# S7G7_footprint_simplified_w_ethernet_v1p.net
KiCad netlist of a schematic drawn in EAGLE
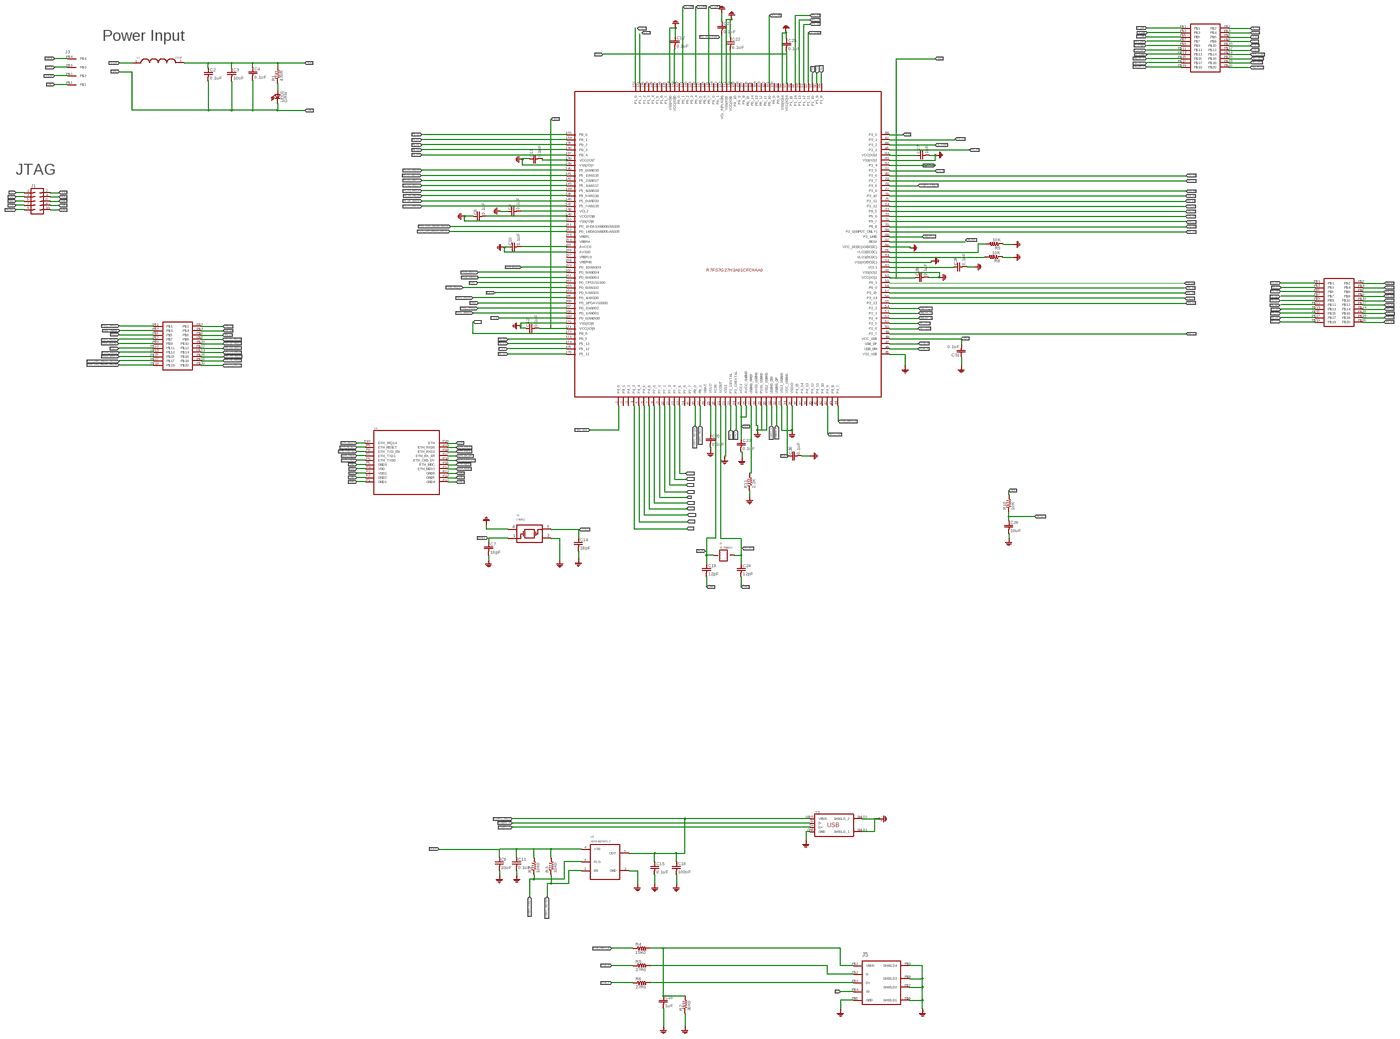
[diagram p0: schematic, sheet 1, overview]
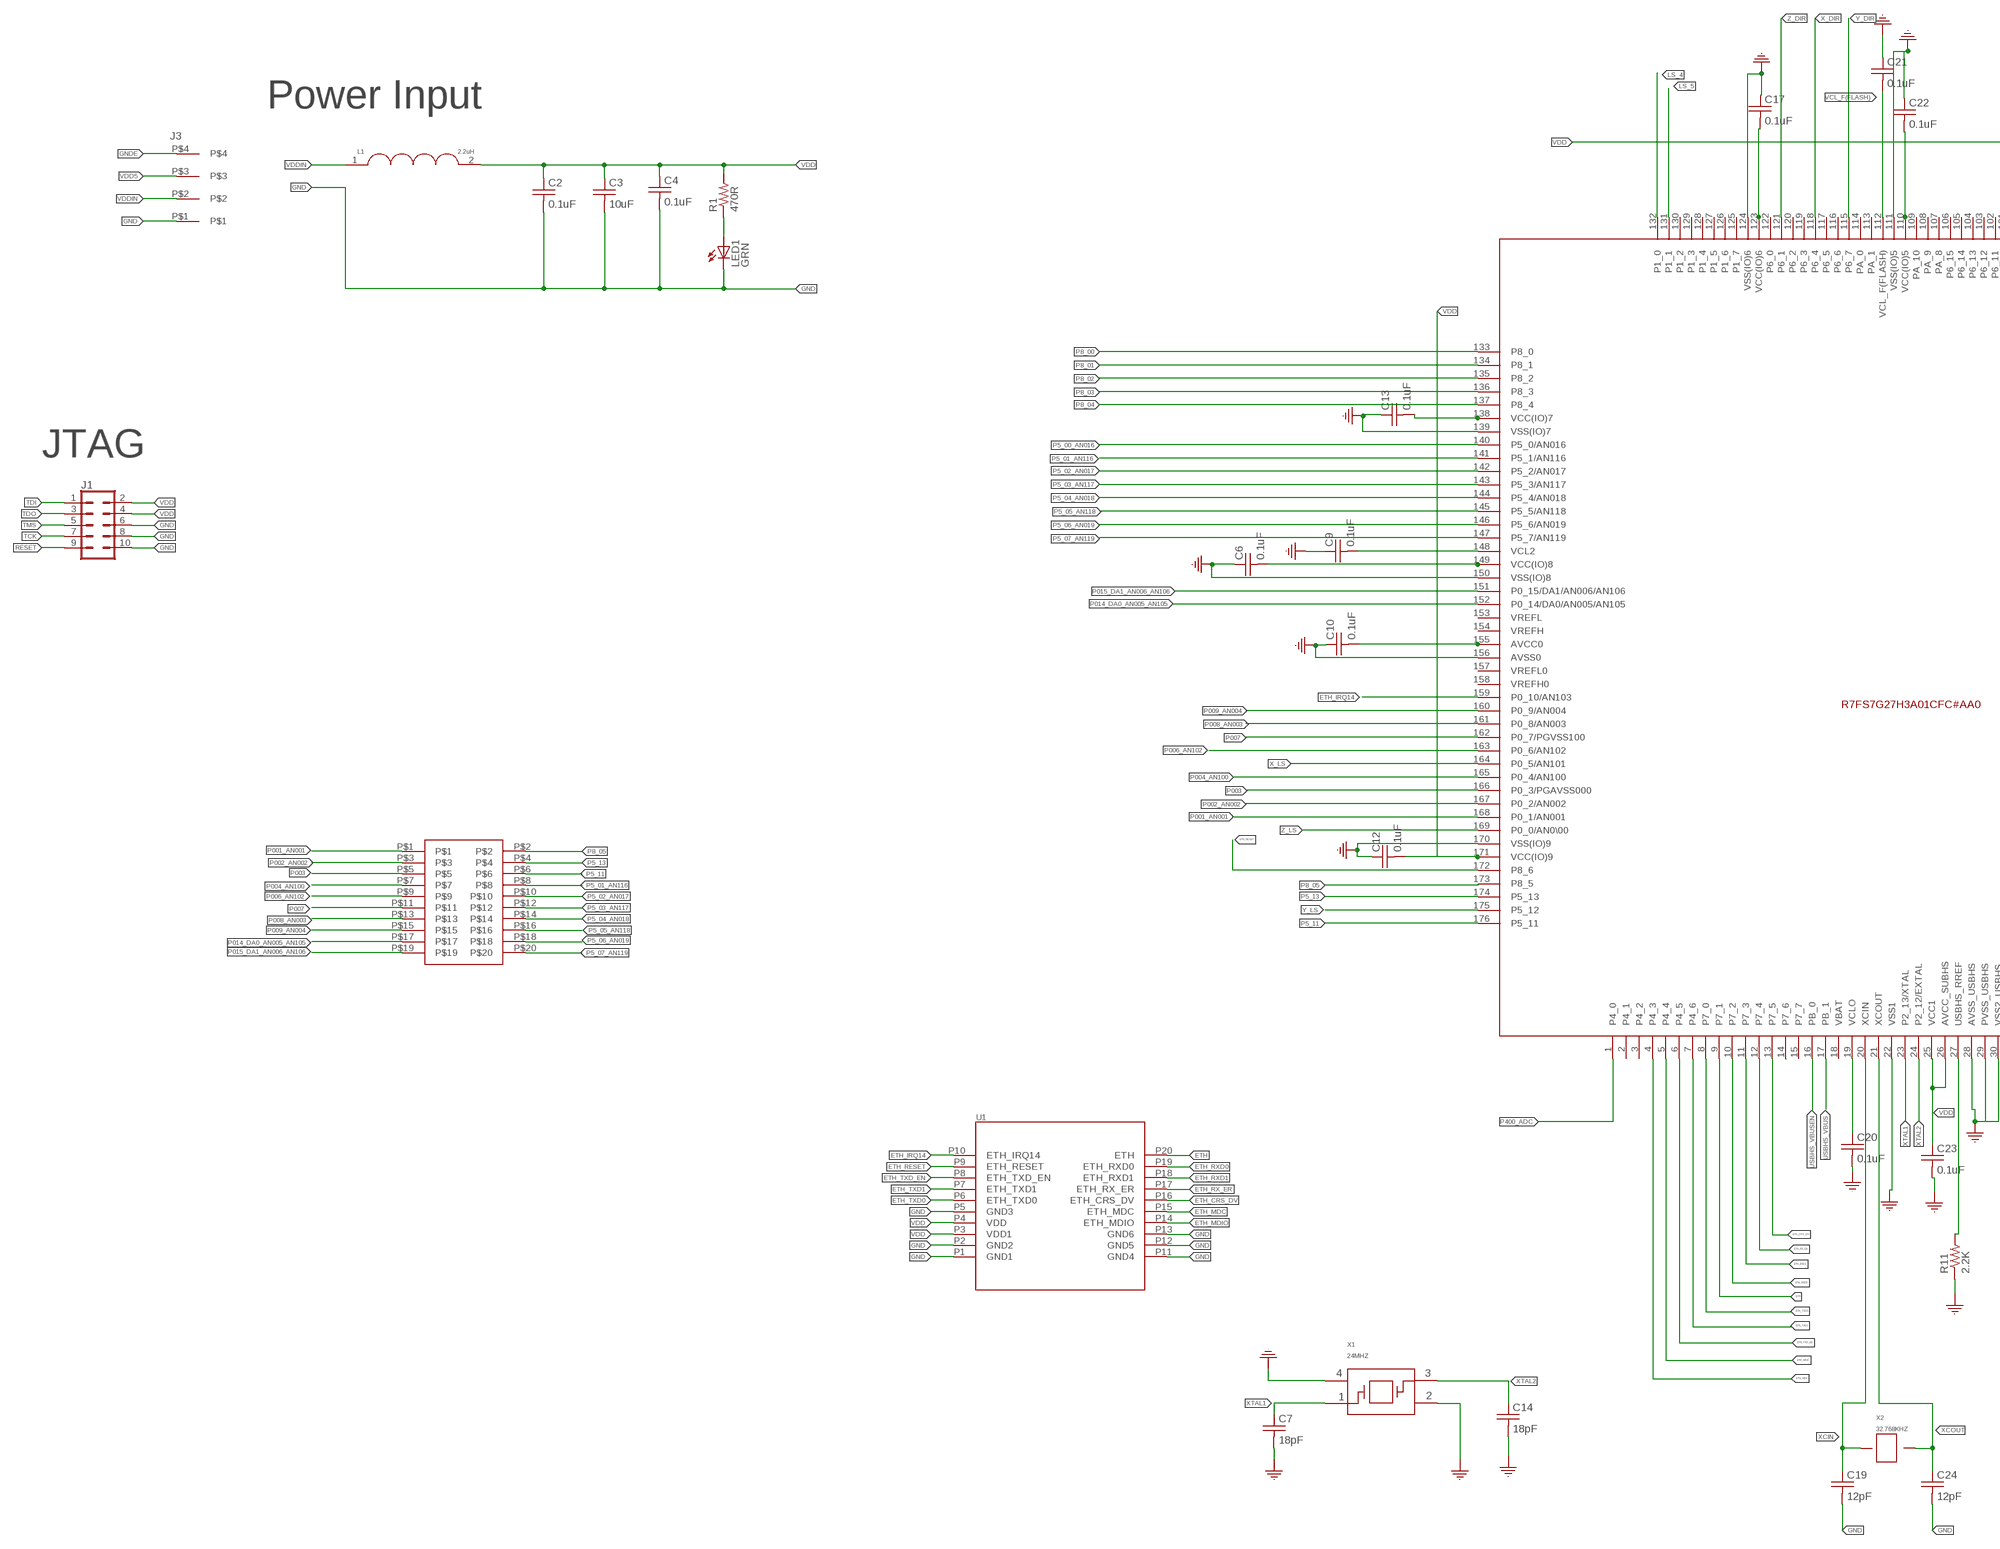
[diagram p1: schematic, sheet 1, part 1 of 4]
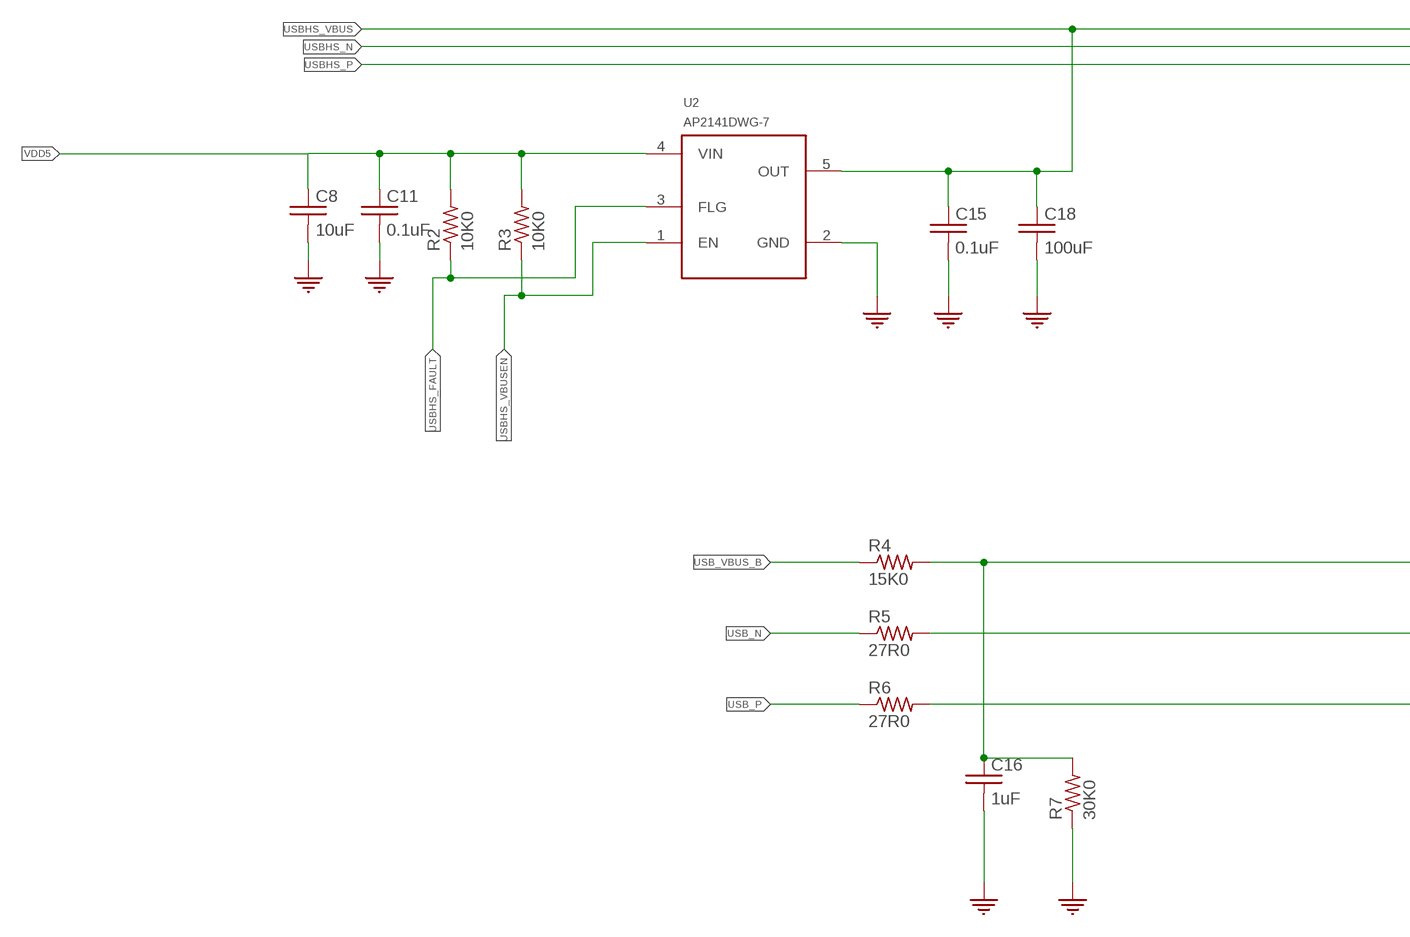
[diagram p2: schematic, sheet 1, part 2 of 4]
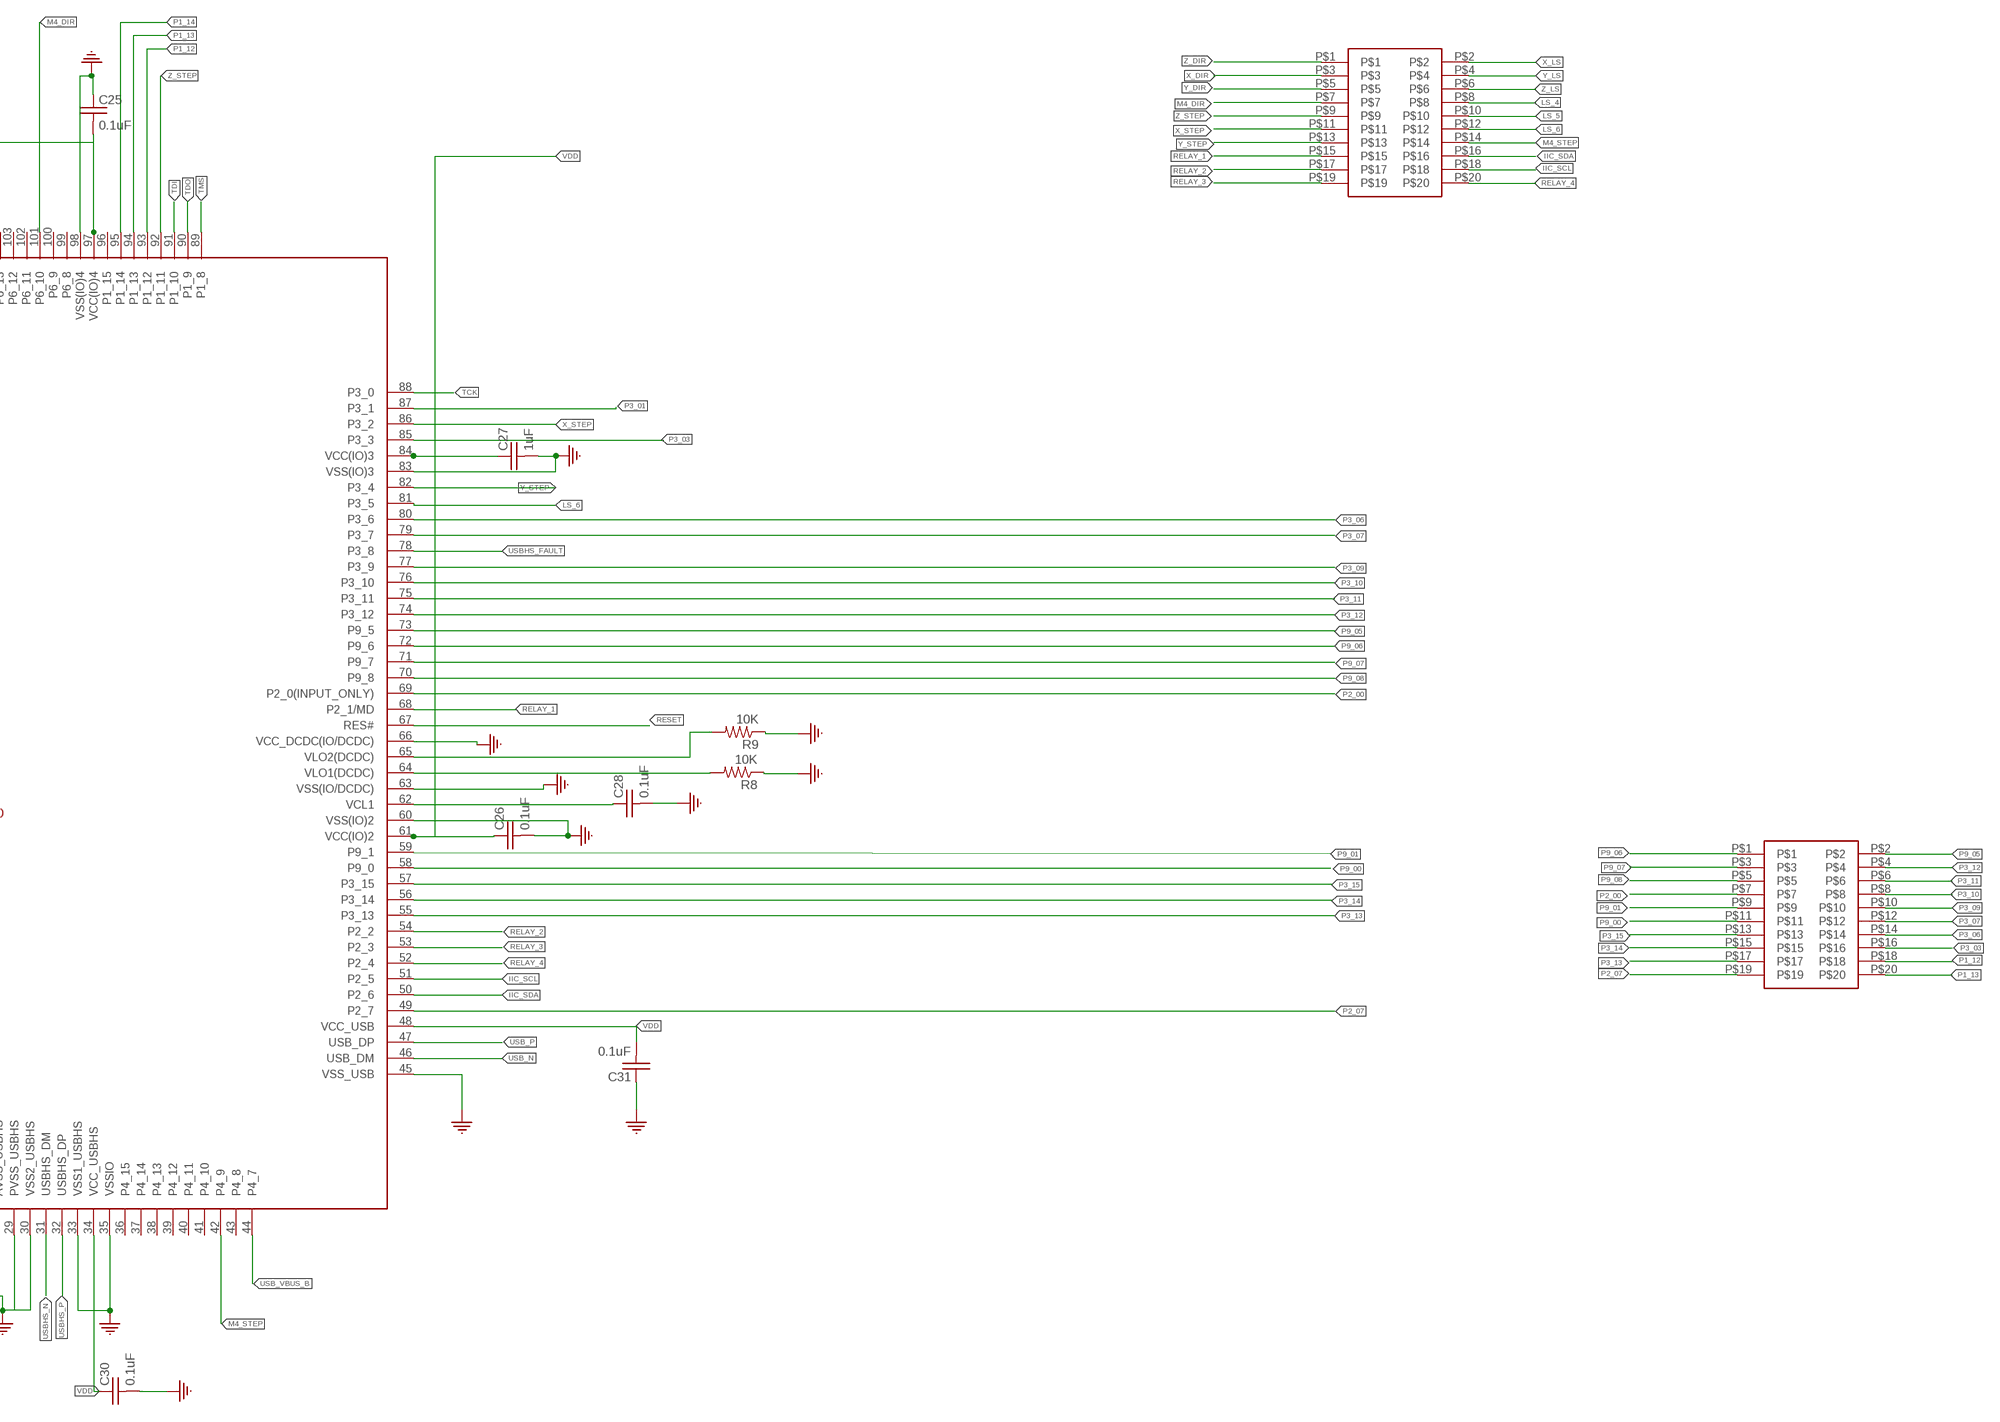
[diagram p3: schematic, sheet 1, part 3 of 4]
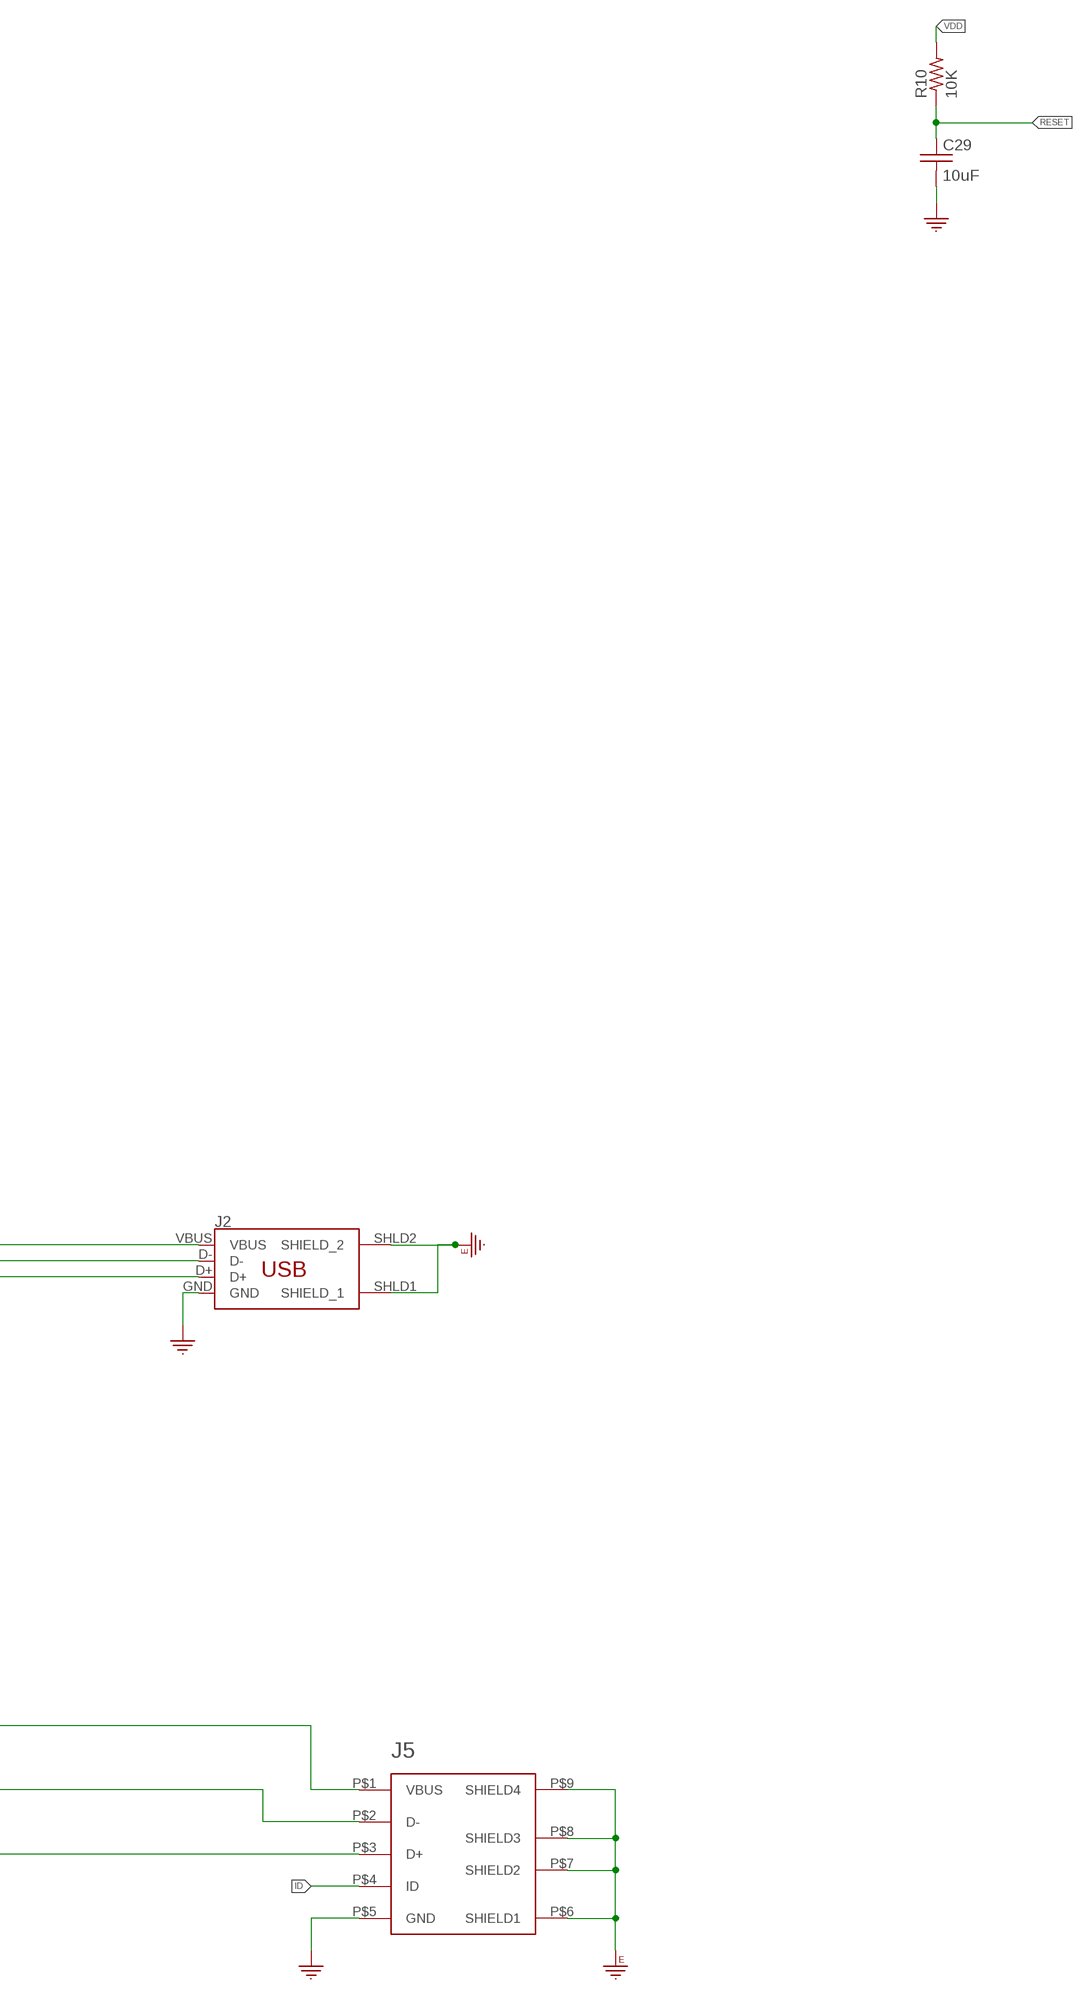
[diagram p4: schematic, sheet 1, part 4 of 4]

(export (version "E")
  (design (tool "Eeschema 10.0.6"))
  (components
    (comp (ref "C2")
      (value "0.1uF")
      (footprint "eagle-import:0402")
      (libsource (lib "eagle-import") (part "C_0402"))
    )
    (comp (ref "C3")
      (value "10uF")
      (footprint "eagle-import:0402")
      (libsource (lib "eagle-import") (part "C_0402"))
    )
    (comp (ref "C4")
      (value "0.1uF")
      (footprint "eagle-import:0402")
      (libsource (lib "eagle-import") (part "C_0402"))
    )
    (comp (ref "C6")
      (value "0.1uF")
      (footprint "eagle-import:0402")
      (libsource (lib "eagle-import") (part "C_0402"))
    )
    (comp (ref "C7")
      (value "18pF")
      (footprint "eagle-import:0402")
      (libsource (lib "eagle-import") (part "C_0402"))
    )
    (comp (ref "C8")
      (value "10uF")
      (footprint "eagle-import:0402")
      (libsource (lib "eagle-import") (part "C_0402"))
    )
    (comp (ref "C9")
      (value "0.1uF")
      (footprint "eagle-import:0402")
      (libsource (lib "eagle-import") (part "C_0402"))
    )
    (comp (ref "C10")
      (value "0.1uF")
      (footprint "eagle-import:0402")
      (libsource (lib "eagle-import") (part "C_0402"))
    )
    (comp (ref "C11")
      (value "0.1uF")
      (footprint "eagle-import:0402")
      (libsource (lib "eagle-import") (part "C_0402"))
    )
    (comp (ref "C12")
      (value "0.1uF")
      (footprint "eagle-import:0402")
      (libsource (lib "eagle-import") (part "C_0402"))
    )
    (comp (ref "C13")
      (value "0.1uF")
      (footprint "eagle-import:0402")
      (libsource (lib "eagle-import") (part "C_0402"))
    )
    (comp (ref "C14")
      (value "18pF")
      (footprint "eagle-import:0402")
      (libsource (lib "eagle-import") (part "C_0402"))
    )
    (comp (ref "C15")
      (value "0.1uF")
      (footprint "eagle-import:0402")
      (libsource (lib "eagle-import") (part "C_0402"))
    )
    (comp (ref "C16")
      (value "1uF")
      (footprint "eagle-import:0402")
      (libsource (lib "eagle-import") (part "C_0402"))
    )
    (comp (ref "C17")
      (value "0.1uF")
      (footprint "eagle-import:0402")
      (libsource (lib "eagle-import") (part "C_0402"))
    )
    (comp (ref "C18")
      (value "100uF")
      (footprint "eagle-import:C1210")
      (libsource (lib "eagle-import") (part "C_1210"))
    )
    (comp (ref "C19")
      (value "12pF")
      (footprint "eagle-import:0402")
      (libsource (lib "eagle-import") (part "C_0402"))
    )
    (comp (ref "C20")
      (value "0.1uF")
      (footprint "eagle-import:0402")
      (libsource (lib "eagle-import") (part "C_0402"))
    )
    (comp (ref "C21")
      (value "0.1uF")
      (footprint "eagle-import:0402")
      (libsource (lib "eagle-import") (part "C_0402"))
    )
    (comp (ref "C22")
      (value "0.1uF")
      (footprint "eagle-import:0402")
      (libsource (lib "eagle-import") (part "C_0402"))
    )
    (comp (ref "C23")
      (value "0.1uF")
      (footprint "eagle-import:0402")
      (libsource (lib "eagle-import") (part "C_0402"))
    )
    (comp (ref "C24")
      (value "12pF")
      (footprint "eagle-import:0402")
      (libsource (lib "eagle-import") (part "C_0402"))
    )
    (comp (ref "C25")
      (value "0.1uF")
      (footprint "eagle-import:0402")
      (libsource (lib "eagle-import") (part "C_0402"))
    )
    (comp (ref "C26")
      (value "0.1uF")
      (footprint "eagle-import:0402")
      (libsource (lib "eagle-import") (part "C_0402"))
    )
    (comp (ref "C27")
      (value "1uF")
      (footprint "eagle-import:0402")
      (libsource (lib "eagle-import") (part "C_0402"))
    )
    (comp (ref "C28")
      (value "0.1uF")
      (footprint "eagle-import:0402")
      (libsource (lib "eagle-import") (part "C_0402"))
    )
    (comp (ref "C29")
      (value "10uF")
      (footprint "eagle-import:0402")
      (libsource (lib "eagle-import") (part "C_0402"))
    )
    (comp (ref "C30")
      (value "0.1uF")
      (footprint "eagle-import:0402")
      (libsource (lib "eagle-import") (part "C_0402"))
    )
    (comp (ref "C31")
      (value "0.1uF")
      (footprint "eagle-import:0402")
      (libsource (lib "eagle-import") (part "C_0402"))
    )
    (comp (ref "J1")
      (value "CONN_05X2PTH")
      (footprint "eagle-import:2X5")
      (libsource (lib "eagle-import") (part "CONN_05X2PTH"))
    )
    (comp (ref "J2")
      (value "USB_A")
      (footprint "eagle-import:USB_A_SMT")
      (libsource (lib "eagle-import") (part "USB_A"))
    )
    (comp (ref "J3")
      (value "3.81MM_1_X_4_RT_ANGLE_PLUG_HEADER")
      (footprint "eagle-import:1X4_3.81MM_PITCH")
      (libsource (lib "eagle-import") (part "3.81MM_1_X_4_RT_ANGLE_PLUG_HEADER"))
    )
    (comp (ref "J4")
      (value "2_X_10_HEADER_GENERIC")
      (footprint "eagle-import:2_X_10_.1_INCH")
      (libsource (lib "eagle-import") (part "2_X_10_HEADER_GENERIC"))
    )
    (comp (ref "J5")
      (value "USB_MICRO-B")
      (footprint "eagle-import:USB_MICRO-B")
      (libsource (lib "eagle-import") (part "USB_MICRO-B"))
    )
    (comp (ref "J7")
      (value "2_X_10_HEADER_GENERIC")
      (footprint "eagle-import:2_X_10_.1_INCH")
      (libsource (lib "eagle-import") (part "2_X_10_HEADER_GENERIC"))
    )
    (comp (ref "J8")
      (value "2_X_10_HEADER_GENERIC")
      (footprint "eagle-import:2_X_10_.1_INCH")
      (libsource (lib "eagle-import") (part "2_X_10_HEADER_GENERIC"))
    )
    (comp (ref "L1")
      (value "2.2uH")
      (footprint "eagle-import:1008_(2520_METRIC)")
      (libsource (lib "eagle-import") (part "INDUCTOR_1008_2.2_MH_1.3A"))
    )
    (comp (ref "LED1")
      (value "LED_0805_GREEN")
      (footprint "eagle-import:LED_0805_GREEN")
      (libsource (lib "eagle-import") (part "LED_0805_GREEN"))
    )
    (comp (ref "R1")
      (value "470R")
      (footprint "eagle-import:0402")
      (libsource (lib "eagle-import") (part "R_0402"))
    )
    (comp (ref "R2")
      (value "10K0")
      (footprint "eagle-import:0402")
      (libsource (lib "eagle-import") (part "R_0402"))
    )
    (comp (ref "R3")
      (value "10K0")
      (footprint "eagle-import:0402")
      (libsource (lib "eagle-import") (part "R_0402"))
    )
    (comp (ref "R4")
      (value "15K0")
      (footprint "eagle-import:0402")
      (libsource (lib "eagle-import") (part "R_0402"))
    )
    (comp (ref "R5")
      (value "27R0")
      (footprint "eagle-import:0402")
      (libsource (lib "eagle-import") (part "R_0402"))
    )
    (comp (ref "R6")
      (value "27R0")
      (footprint "eagle-import:0402")
      (libsource (lib "eagle-import") (part "R_0402"))
    )
    (comp (ref "R7")
      (value "30K0")
      (footprint "eagle-import:0402")
      (libsource (lib "eagle-import") (part "R_0402"))
    )
    (comp (ref "R8")
      (value "10K")
      (footprint "eagle-import:0402")
      (libsource (lib "eagle-import") (part "R_0402"))
    )
    (comp (ref "R9")
      (value "10K")
      (footprint "eagle-import:0402")
      (libsource (lib "eagle-import") (part "R_0402"))
    )
    (comp (ref "R10")
      (value "10K")
      (footprint "eagle-import:0402")
      (libsource (lib "eagle-import") (part "R_0402"))
    )
    (comp (ref "R11")
      (value "2.2K")
      (footprint "eagle-import:0402")
      (libsource (lib "eagle-import") (part "R_0402"))
    )
    (comp (ref "U1")
      (value "ETHERNET_HAT")
      (footprint "eagle-import:ETHERNET_HAT")
      (libsource (lib "eagle-import") (part "ETHERNET_HAT"))
    )
    (comp (ref "U2")
      (value "AP2141DWG-5")
      (footprint "eagle-import:SOT-23-5")
      (libsource (lib "eagle-import") (part "AP2141DWG-5"))
    )
    (comp (ref "U5")
      (value "S7G2_X_176")
      (footprint "eagle-import:LQFP176_24X24")
      (libsource (lib "eagle-import") (part "S7G2_X_176"))
    )
    (comp (ref "X1")
      (value "24MHZ")
      (footprint "eagle-import:SMD_3225")
      (libsource (lib "eagle-import") (part "XTAL_24_MHZ"))
    )
    (comp (ref "X2")
      (value "32.768KHZ")
      (footprint "eagle-import:SMD_X_2_PADS")
      (libsource (lib "eagle-import") (part "XTAL_32.768KHZ"))
    )
  )
  (nets
    (net (code "1") (name "ETH") (class "Default")
      (node (ref "U1") (pin "P20") (pinfunction "ETH_P20") (pintype "bidirectional"))
      (node (ref "U5") (pin "9") (pinfunction "P7_1_9") (pintype "bidirectional"))
    )
    (net (code "2") (name "ETH_CRS_DV") (class "Default")
      (node (ref "U1") (pin "P16") (pinfunction "ETH_CRS_DV_P16") (pintype "bidirectional"))
      (node (ref "U5") (pin "13") (pinfunction "P7_5_13") (pintype "bidirectional"))
    )
    (net (code "3") (name "ETH_IRQ14") (class "Default")
      (node (ref "U1") (pin "P10") (pinfunction "ETH_IRQ14_P10") (pintype "bidirectional"))
      (node (ref "U5") (pin "159") (pinfunction "P0_10/AN103_159") (pintype "bidirectional"))
    )
    (net (code "4") (name "ETH_MDC") (class "Default")
      (node (ref "U1") (pin "P15") (pinfunction "ETH_MDC_P15") (pintype "bidirectional"))
      (node (ref "U5") (pin "4") (pinfunction "P4_3_4") (pintype "bidirectional"))
    )
    (net (code "5") (name "ETH_MDIO") (class "Default")
      (node (ref "U1") (pin "P14") (pinfunction "ETH_MDIO_P14") (pintype "bidirectional"))
      (node (ref "U5") (pin "5") (pinfunction "P4_4_5") (pintype "bidirectional"))
    )
    (net (code "6") (name "ETH_RESET") (class "Default")
      (node (ref "U1") (pin "P9") (pinfunction "ETH_RESET_P9") (pintype "bidirectional"))
      (node (ref "U5") (pin "172") (pinfunction "P8_6_172") (pintype "bidirectional"))
    )
    (net (code "7") (name "ETH_RXD0") (class "Default")
      (node (ref "U1") (pin "P19") (pinfunction "ETH_RXD0_P19") (pintype "bidirectional"))
      (node (ref "U5") (pin "10") (pinfunction "P7_2_10") (pintype "bidirectional"))
    )
    (net (code "8") (name "ETH_RXD1") (class "Default")
      (node (ref "U1") (pin "P18") (pinfunction "ETH_RXD1_P18") (pintype "bidirectional"))
      (node (ref "U5") (pin "11") (pinfunction "P7_3_11") (pintype "bidirectional"))
    )
    (net (code "9") (name "ETH_RX_ER") (class "Default")
      (node (ref "U1") (pin "P17") (pinfunction "ETH_RX_ER_P17") (pintype "bidirectional"))
      (node (ref "U5") (pin "12") (pinfunction "P7_4_12") (pintype "bidirectional"))
    )
    (net (code "10") (name "ETH_TXD0") (class "Default")
      (node (ref "U1") (pin "P6") (pinfunction "ETH_TXD0_P6") (pintype "bidirectional"))
      (node (ref "U5") (pin "8") (pinfunction "P7_0_8") (pintype "bidirectional"))
    )
    (net (code "11") (name "ETH_TXD1") (class "Default")
      (node (ref "U1") (pin "P7") (pinfunction "ETH_TXD1_P7") (pintype "bidirectional"))
      (node (ref "U5") (pin "7") (pinfunction "P4_6_7") (pintype "bidirectional"))
    )
    (net (code "12") (name "ETH_TXD_EN") (class "Default")
      (node (ref "U1") (pin "P8") (pinfunction "ETH_TXD_EN_P8") (pintype "bidirectional"))
      (node (ref "U5") (pin "6") (pinfunction "P4_5_6") (pintype "bidirectional"))
    )
    (net (code "13") (name "GND") (class "Default")
      (node (ref "C10") (pin "P$1") (pinfunction "1_P$1") (pintype "passive"))
      (node (ref "C11") (pin "P$2") (pinfunction "2_P$2") (pintype "passive"))
      (node (ref "C12") (pin "P$1") (pinfunction "1_P$1") (pintype "passive"))
      (node (ref "C13") (pin "P$1") (pinfunction "1_P$1") (pintype "passive"))
      (node (ref "C14") (pin "P$2") (pinfunction "2_P$2") (pintype "passive"))
      (node (ref "C15") (pin "P$2") (pinfunction "2_P$2") (pintype "passive"))
      (node (ref "C16") (pin "P$2") (pinfunction "2_P$2") (pintype "passive"))
      (node (ref "C17") (pin "P$1") (pinfunction "1_P$1") (pintype "passive"))
      (node (ref "C18") (pin "2") (pinfunction "2_2") (pintype "passive"))
      (node (ref "C19") (pin "P$2") (pinfunction "2_P$2") (pintype "passive"))
      (node (ref "C2") (pin "P$2") (pinfunction "2_P$2") (pintype "passive"))
      (node (ref "C20") (pin "P$2") (pinfunction "2_P$2") (pintype "passive"))
      (node (ref "C21") (pin "P$1") (pinfunction "1_P$1") (pintype "passive"))
      (node (ref "C22") (pin "P$1") (pinfunction "1_P$1") (pintype "passive"))
      (node (ref "C23") (pin "P$2") (pinfunction "2_P$2") (pintype "passive"))
      (node (ref "C24") (pin "P$2") (pinfunction "2_P$2") (pintype "passive"))
      (node (ref "C25") (pin "P$1") (pinfunction "1_P$1") (pintype "passive"))
      (node (ref "C26") (pin "P$2") (pinfunction "2_P$2") (pintype "passive"))
      (node (ref "C27") (pin "P$2") (pinfunction "2_P$2") (pintype "passive"))
      (node (ref "C28") (pin "P$2") (pinfunction "2_P$2") (pintype "passive"))
      (node (ref "C29") (pin "P$2") (pinfunction "2_P$2") (pintype "passive"))
      (node (ref "C3") (pin "P$2") (pinfunction "2_P$2") (pintype "passive"))
      (node (ref "C30") (pin "P$2") (pinfunction "2_P$2") (pintype "passive"))
      (node (ref "C31") (pin "P$1") (pinfunction "1_P$1") (pintype "passive"))
      (node (ref "C4") (pin "P$2") (pinfunction "2_P$2") (pintype "passive"))
      (node (ref "C6") (pin "P$1") (pinfunction "1_P$1") (pintype "passive"))
      (node (ref "C7") (pin "P$2") (pinfunction "2_P$2") (pintype "passive"))
      (node (ref "C8") (pin "P$2") (pinfunction "2_P$2") (pintype "passive"))
      (node (ref "C9") (pin "P$1") (pinfunction "1_P$1") (pintype "passive"))
      (node (ref "J1") (pin "10") (pinfunction "10_10") (pintype "passive"))
      (node (ref "J1") (pin "6") (pinfunction "6_6") (pintype "passive"))
      (node (ref "J1") (pin "8") (pinfunction "8_8") (pintype "passive"))
      (node (ref "J2") (pin "GND") (pinfunction "GND_GND") (pintype "power_in"))
      (node (ref "J3") (pin "P$1") (pinfunction "P$1_P$1") (pintype "bidirectional"))
      (node (ref "J5") (pin "P$5") (pinfunction "GND_P$5") (pintype "bidirectional"))
      (node (ref "LED1") (pin "C") (pinfunction "C_C") (pintype "passive"))
      (node (ref "R11") (pin "P$1") (pinfunction "1_P$1") (pintype "passive"))
      (node (ref "R7") (pin "P$1") (pinfunction "1_P$1") (pintype "passive"))
      (node (ref "R8") (pin "P$1") (pinfunction "1_P$1") (pintype "passive"))
      (node (ref "R9") (pin "P$1") (pinfunction "1_P$1") (pintype "passive"))
      (node (ref "U1") (pin "P1") (pinfunction "GND1_P1") (pintype "bidirectional"))
      (node (ref "U1") (pin "P11") (pinfunction "GND4_P11") (pintype "bidirectional"))
      (node (ref "U1") (pin "P12") (pinfunction "GND5_P12") (pintype "bidirectional"))
      (node (ref "U1") (pin "P13") (pinfunction "GND6_P13") (pintype "bidirectional"))
      (node (ref "U1") (pin "P2") (pinfunction "GND2_P2") (pintype "bidirectional"))
      (node (ref "U1") (pin "P5") (pinfunction "GND3_P5") (pintype "bidirectional"))
      (node (ref "U2") (pin "2") (pinfunction "GND_2") (pintype "input"))
      (node (ref "U5") (pin "111") (pinfunction "VSS(IO)5_111") (pintype "bidirectional"))
      (node (ref "U5") (pin "124") (pinfunction "VSS(IO)6_124") (pintype "bidirectional"))
      (node (ref "U5") (pin "139") (pinfunction "VSS(IO)7_139") (pintype "bidirectional"))
      (node (ref "U5") (pin "150") (pinfunction "VSS(IO)8_150") (pintype "bidirectional"))
      (node (ref "U5") (pin "156") (pinfunction "AVSS0_156") (pintype "bidirectional"))
      (node (ref "U5") (pin "170") (pinfunction "VSS(IO)9_170") (pintype "bidirectional"))
      (node (ref "U5") (pin "22") (pinfunction "VSS1_22") (pintype "bidirectional"))
      (node (ref "U5") (pin "28") (pinfunction "AVSS_USBHS_28") (pintype "bidirectional"))
      (node (ref "U5") (pin "29") (pinfunction "PVSS_USBHS_29") (pintype "bidirectional"))
      (node (ref "U5") (pin "30") (pinfunction "VSS2_USBHS_30") (pintype "bidirectional"))
      (node (ref "U5") (pin "33") (pinfunction "VSS1_USBHS_33") (pintype "bidirectional"))
      (node (ref "U5") (pin "35") (pinfunction "VSSIO_35") (pintype "bidirectional"))
      (node (ref "U5") (pin "45") (pinfunction "VSS_USB_45") (pintype "bidirectional"))
      (node (ref "U5") (pin "60") (pinfunction "VSS(IO)2_60") (pintype "bidirectional"))
      (node (ref "U5") (pin "63") (pinfunction "VSS(IO/DCDC)_63") (pintype "bidirectional"))
      (node (ref "U5") (pin "66") (pinfunction "VCC_DCDC(IO/DCDC)_66") (pintype "bidirectional"))
      (node (ref "U5") (pin "83") (pinfunction "VSS(IO)3_83") (pintype "bidirectional"))
      (node (ref "U5") (pin "98") (pinfunction "VSS(IO)4_98") (pintype "bidirectional"))
      (node (ref "X1") (pin "2") (pinfunction "2_2") (pintype "bidirectional"))
      (node (ref "X1") (pin "4") (pinfunction "4_4") (pintype "bidirectional"))
    )
    (net (code "14") (name "GNDE") (class "Default")
      (node (ref "J2") (pin "SHLD1") (pinfunction "SHIELD_1_SHLD1") (pintype "bidirectional"))
      (node (ref "J2") (pin "SHLD2") (pinfunction "SHIELD_2_SHLD2") (pintype "bidirectional"))
      (node (ref "J3") (pin "P$4") (pinfunction "P$4_P$4") (pintype "bidirectional"))
      (node (ref "J5") (pin "P$6") (pinfunction "SHIELD1_P$6") (pintype "bidirectional"))
      (node (ref "J5") (pin "P$7") (pinfunction "SHIELD2_P$7") (pintype "bidirectional"))
      (node (ref "J5") (pin "P$8") (pinfunction "SHIELD3_P$8") (pintype "bidirectional"))
      (node (ref "J5") (pin "P$9") (pinfunction "SHIELD4_P$9") (pintype "bidirectional"))
    )
    (net (code "15") (name "ID") (class "Default")
      (node (ref "J5") (pin "P$4") (pinfunction "ID_P$4") (pintype "bidirectional"))
    )
    (net (code "16") (name "IIC_SCL") (class "Default")
      (node (ref "J4") (pin "P$18") (pinfunction "P$18_P$18") (pintype "bidirectional"))
      (node (ref "U5") (pin "51") (pinfunction "P2_5_51") (pintype "bidirectional"))
    )
    (net (code "17") (name "IIC_SDA") (class "Default")
      (node (ref "J4") (pin "P$16") (pinfunction "P$16_P$16") (pintype "bidirectional"))
      (node (ref "U5") (pin "50") (pinfunction "P2_6_50") (pintype "bidirectional"))
    )
    (net (code "18") (name "LS_4") (class "Default")
      (node (ref "J4") (pin "P$8") (pinfunction "P$8_P$8") (pintype "bidirectional"))
      (node (ref "U5") (pin "132") (pinfunction "P1_0_132") (pintype "bidirectional"))
    )
    (net (code "19") (name "LS_5") (class "Default")
      (node (ref "J4") (pin "P$10") (pinfunction "P$10_P$10") (pintype "bidirectional"))
      (node (ref "U5") (pin "131") (pinfunction "P1_1_131") (pintype "bidirectional"))
    )
    (net (code "20") (name "LS_6") (class "Default")
      (node (ref "J4") (pin "P$12") (pinfunction "P$12_P$12") (pintype "bidirectional"))
      (node (ref "U5") (pin "81") (pinfunction "P3_5_81") (pintype "bidirectional"))
    )
    (net (code "21") (name "M4_DIR") (class "Default")
      (node (ref "J4") (pin "P$7") (pinfunction "P$7_P$7") (pintype "bidirectional"))
      (node (ref "U5") (pin "101") (pinfunction "P6_10_101") (pintype "bidirectional"))
    )
    (net (code "22") (name "M4_STEP") (class "Default")
      (node (ref "J4") (pin "P$14") (pinfunction "P$14_P$14") (pintype "bidirectional"))
      (node (ref "U5") (pin "42") (pinfunction "P4_9_42") (pintype "bidirectional"))
    )
    (net (code "23") (name "Net-(C9-2)") (class "Default")
      (node (ref "C9") (pin "P$2") (pinfunction "2_P$2") (pintype "passive"))
      (node (ref "U5") (pin "148") (pinfunction "VCL2_148") (pintype "bidirectional"))
    )
    (net (code "24") (name "Net-(C16-1)") (class "Default")
      (node (ref "C16") (pin "P$1") (pinfunction "1_P$1") (pintype "passive"))
      (node (ref "J5") (pin "P$1") (pinfunction "VBUS_P$1") (pintype "bidirectional"))
      (node (ref "R4") (pin "P$2") (pinfunction "2_P$2") (pintype "passive"))
      (node (ref "R7") (pin "P$2") (pinfunction "2_P$2") (pintype "passive"))
    )
    (net (code "25") (name "Net-(C20-1)") (class "Default")
      (node (ref "C20") (pin "P$1") (pinfunction "1_P$1") (pintype "passive"))
      (node (ref "U5") (pin "19") (pinfunction "VCLO_19") (pintype "bidirectional"))
    )
    (net (code "26") (name "Net-(C28-1)") (class "Default")
      (node (ref "C28") (pin "P$1") (pinfunction "1_P$1") (pintype "passive"))
      (node (ref "U5") (pin "62") (pinfunction "VCL1_62") (pintype "bidirectional"))
    )
    (net (code "27") (name "Net-(J5-D+)") (class "Default")
      (node (ref "J5") (pin "P$3") (pinfunction "D+_P$3") (pintype "bidirectional"))
      (node (ref "R6") (pin "P$2") (pinfunction "2_P$2") (pintype "passive"))
    )
    (net (code "28") (name "Net-(J5-D-)") (class "Default")
      (node (ref "J5") (pin "P$2") (pinfunction "D-_P$2") (pintype "bidirectional"))
      (node (ref "R5") (pin "P$2") (pinfunction "2_P$2") (pintype "passive"))
    )
    (net (code "29") (name "Net-(R1-1)") (class "Default")
      (node (ref "LED1") (pin "A") (pinfunction "A_A") (pintype "passive"))
      (node (ref "R1") (pin "P$1") (pinfunction "1_P$1") (pintype "passive"))
    )
    (net (code "30") (name "Net-(R8-2)") (class "Default")
      (node (ref "R8") (pin "P$2") (pinfunction "2_P$2") (pintype "passive"))
      (node (ref "U5") (pin "64") (pinfunction "VLO1(DCDC)_64") (pintype "bidirectional"))
    )
    (net (code "31") (name "Net-(R9-2)") (class "Default")
      (node (ref "R9") (pin "P$2") (pinfunction "2_P$2") (pintype "passive"))
      (node (ref "U5") (pin "65") (pinfunction "VLO2(DCDC)_65") (pintype "bidirectional"))
    )
    (net (code "32") (name "Net-(R11-2)") (class "Default")
      (node (ref "R11") (pin "P$2") (pinfunction "2_P$2") (pintype "passive"))
      (node (ref "U5") (pin "27") (pinfunction "USBHS_RREF_27") (pintype "bidirectional"))
    )
    (net (code "33") (name "P1_12") (class "Default")
      (node (ref "J7") (pin "P$18") (pinfunction "P$18_P$18") (pintype "bidirectional"))
      (node (ref "U5") (pin "93") (pinfunction "P1_12_93") (pintype "bidirectional"))
    )
    (net (code "34") (name "P1_13") (class "Default")
      (node (ref "J7") (pin "P$20") (pinfunction "P$20_P$20") (pintype "bidirectional"))
      (node (ref "U5") (pin "94") (pinfunction "P1_13_94") (pintype "bidirectional"))
    )
    (net (code "35") (name "P1_14") (class "Default")
      (node (ref "U5") (pin "95") (pinfunction "P1_14_95") (pintype "bidirectional"))
    )
    (net (code "36") (name "P001_AN001") (class "Default")
      (node (ref "J8") (pin "P$1") (pinfunction "P$1_P$1") (pintype "bidirectional"))
      (node (ref "U5") (pin "168") (pinfunction "P0_1/AN001_168") (pintype "bidirectional"))
    )
    (net (code "37") (name "P2_00") (class "Default")
      (node (ref "J7") (pin "P$7") (pinfunction "P$7_P$7") (pintype "bidirectional"))
      (node (ref "U5") (pin "69") (pinfunction "P2_0(INPUT_ONLY)_69") (pintype "bidirectional"))
    )
    (net (code "38") (name "P2_07") (class "Default")
      (node (ref "J7") (pin "P$19") (pinfunction "P$19_P$19") (pintype "bidirectional"))
      (node (ref "U5") (pin "49") (pinfunction "P2_7_49") (pintype "bidirectional"))
    )
    (net (code "39") (name "P002_AN002") (class "Default")
      (node (ref "J8") (pin "P$3") (pinfunction "P$3_P$3") (pintype "bidirectional"))
      (node (ref "U5") (pin "167") (pinfunction "P0_2/AN002_167") (pintype "bidirectional"))
    )
    (net (code "40") (name "P003") (class "Default")
      (node (ref "J8") (pin "P$5") (pinfunction "P$5_P$5") (pintype "bidirectional"))
      (node (ref "U5") (pin "166") (pinfunction "P0_3/PGAVSS000_166") (pintype "bidirectional"))
    )
    (net (code "41") (name "P3_01") (class "Default")
      (node (ref "U5") (pin "87") (pinfunction "P3_1_87") (pintype "bidirectional"))
    )
    (net (code "42") (name "P3_03") (class "Default")
      (node (ref "J7") (pin "P$16") (pinfunction "P$16_P$16") (pintype "bidirectional"))
      (node (ref "U5") (pin "85") (pinfunction "P3_3_85") (pintype "bidirectional"))
    )
    (net (code "43") (name "P3_06") (class "Default")
      (node (ref "J7") (pin "P$14") (pinfunction "P$14_P$14") (pintype "bidirectional"))
      (node (ref "U5") (pin "80") (pinfunction "P3_6_80") (pintype "bidirectional"))
    )
    (net (code "44") (name "P3_07") (class "Default")
      (node (ref "J7") (pin "P$12") (pinfunction "P$12_P$12") (pintype "bidirectional"))
      (node (ref "U5") (pin "79") (pinfunction "P3_7_79") (pintype "bidirectional"))
    )
    (net (code "45") (name "P3_09") (class "Default")
      (node (ref "J7") (pin "P$10") (pinfunction "P$10_P$10") (pintype "bidirectional"))
      (node (ref "U5") (pin "77") (pinfunction "P3_9_77") (pintype "bidirectional"))
    )
    (net (code "46") (name "P3_10") (class "Default")
      (node (ref "J7") (pin "P$8") (pinfunction "P$8_P$8") (pintype "bidirectional"))
      (node (ref "U5") (pin "76") (pinfunction "P3_10_76") (pintype "bidirectional"))
    )
    (net (code "47") (name "P3_11") (class "Default")
      (node (ref "J7") (pin "P$6") (pinfunction "P$6_P$6") (pintype "bidirectional"))
      (node (ref "U5") (pin "75") (pinfunction "P3_11_75") (pintype "bidirectional"))
    )
    (net (code "48") (name "P3_12") (class "Default")
      (node (ref "J7") (pin "P$4") (pinfunction "P$4_P$4") (pintype "bidirectional"))
      (node (ref "U5") (pin "74") (pinfunction "P3_12_74") (pintype "bidirectional"))
    )
    (net (code "49") (name "P3_13") (class "Default")
      (node (ref "J7") (pin "P$17") (pinfunction "P$17_P$17") (pintype "bidirectional"))
      (node (ref "U5") (pin "55") (pinfunction "P3_13_55") (pintype "bidirectional"))
    )
    (net (code "50") (name "P3_14") (class "Default")
      (node (ref "J7") (pin "P$15") (pinfunction "P$15_P$15") (pintype "bidirectional"))
      (node (ref "U5") (pin "56") (pinfunction "P3_14_56") (pintype "bidirectional"))
    )
    (net (code "51") (name "P3_15") (class "Default")
      (node (ref "J7") (pin "P$13") (pinfunction "P$13_P$13") (pintype "bidirectional"))
      (node (ref "U5") (pin "57") (pinfunction "P3_15_57") (pintype "bidirectional"))
    )
    (net (code "52") (name "P004_AN100") (class "Default")
      (node (ref "J8") (pin "P$7") (pinfunction "P$7_P$7") (pintype "bidirectional"))
      (node (ref "U5") (pin "165") (pinfunction "P0_4/AN100_165") (pintype "bidirectional"))
    )
    (net (code "53") (name "P5_00_AN016") (class "Default")
      (node (ref "U5") (pin "140") (pinfunction "P5_0/AN016_140") (pintype "bidirectional"))
    )
    (net (code "54") (name "P5_01_AN116") (class "Default")
      (node (ref "J8") (pin "P$8") (pinfunction "P$8_P$8") (pintype "bidirectional"))
      (node (ref "U5") (pin "141") (pinfunction "P5_1/AN116_141") (pintype "bidirectional"))
    )
    (net (code "55") (name "P5_02_AN017") (class "Default")
      (node (ref "J8") (pin "P$10") (pinfunction "P$10_P$10") (pintype "bidirectional"))
      (node (ref "U5") (pin "142") (pinfunction "P5_2/AN017_142") (pintype "bidirectional"))
    )
    (net (code "56") (name "P5_03_AN117") (class "Default")
      (node (ref "J8") (pin "P$12") (pinfunction "P$12_P$12") (pintype "bidirectional"))
      (node (ref "U5") (pin "143") (pinfunction "P5_3/AN117_143") (pintype "bidirectional"))
    )
    (net (code "57") (name "P5_04_AN018") (class "Default")
      (node (ref "J8") (pin "P$14") (pinfunction "P$14_P$14") (pintype "bidirectional"))
      (node (ref "U5") (pin "144") (pinfunction "P5_4/AN018_144") (pintype "bidirectional"))
    )
    (net (code "58") (name "P5_05_AN118") (class "Default")
      (node (ref "J8") (pin "P$16") (pinfunction "P$16_P$16") (pintype "bidirectional"))
      (node (ref "U5") (pin "145") (pinfunction "P5_5/AN118_145") (pintype "bidirectional"))
    )
    (net (code "59") (name "P5_06_AN019") (class "Default")
      (node (ref "J8") (pin "P$18") (pinfunction "P$18_P$18") (pintype "bidirectional"))
      (node (ref "U5") (pin "146") (pinfunction "P5_6/AN019_146") (pintype "bidirectional"))
    )
    (net (code "60") (name "P5_07_AN119") (class "Default")
      (node (ref "J8") (pin "P$20") (pinfunction "P$20_P$20") (pintype "bidirectional"))
      (node (ref "U5") (pin "147") (pinfunction "P5_7/AN119_147") (pintype "bidirectional"))
    )
    (net (code "61") (name "P5_11") (class "Default")
      (node (ref "J8") (pin "P$6") (pinfunction "P$6_P$6") (pintype "bidirectional"))
      (node (ref "U5") (pin "176") (pinfunction "P5_11_176") (pintype "bidirectional"))
    )
    (net (code "62") (name "P5_13") (class "Default")
      (node (ref "J8") (pin "P$4") (pinfunction "P$4_P$4") (pintype "bidirectional"))
      (node (ref "U5") (pin "174") (pinfunction "P5_13_174") (pintype "bidirectional"))
    )
    (net (code "63") (name "P006_AN102") (class "Default")
      (node (ref "J8") (pin "P$9") (pinfunction "P$9_P$9") (pintype "bidirectional"))
      (node (ref "U5") (pin "163") (pinfunction "P0_6/AN102_163") (pintype "bidirectional"))
    )
    (net (code "64") (name "P007") (class "Default")
      (node (ref "J8") (pin "P$11") (pinfunction "P$11_P$11") (pintype "bidirectional"))
      (node (ref "U5") (pin "162") (pinfunction "P0_7/PGVSS100_162") (pintype "bidirectional"))
    )
    (net (code "65") (name "P8_00") (class "Default")
      (node (ref "U5") (pin "133") (pinfunction "P8_0_133") (pintype "bidirectional"))
    )
    (net (code "66") (name "P8_01") (class "Default")
      (node (ref "U5") (pin "134") (pinfunction "P8_1_134") (pintype "bidirectional"))
    )
    (net (code "67") (name "P8_02") (class "Default")
      (node (ref "U5") (pin "135") (pinfunction "P8_2_135") (pintype "bidirectional"))
    )
    (net (code "68") (name "P8_03") (class "Default")
      (node (ref "U5") (pin "136") (pinfunction "P8_3_136") (pintype "bidirectional"))
    )
    (net (code "69") (name "P8_04") (class "Default")
      (node (ref "U5") (pin "137") (pinfunction "P8_4_137") (pintype "bidirectional"))
    )
    (net (code "70") (name "P8_05") (class "Default")
      (node (ref "J8") (pin "P$2") (pinfunction "P$2_P$2") (pintype "bidirectional"))
      (node (ref "U5") (pin "173") (pinfunction "P8_5_173") (pintype "bidirectional"))
    )
    (net (code "71") (name "P008_AN003") (class "Default")
      (node (ref "J8") (pin "P$13") (pinfunction "P$13_P$13") (pintype "bidirectional"))
      (node (ref "U5") (pin "161") (pinfunction "P0_8/AN003_161") (pintype "bidirectional"))
    )
    (net (code "72") (name "P9_00") (class "Default")
      (node (ref "J7") (pin "P$11") (pinfunction "P$11_P$11") (pintype "bidirectional"))
      (node (ref "U5") (pin "58") (pinfunction "P9_0_58") (pintype "bidirectional"))
    )
    (net (code "73") (name "P9_01") (class "Default")
      (node (ref "J7") (pin "P$9") (pinfunction "P$9_P$9") (pintype "bidirectional"))
      (node (ref "U5") (pin "59") (pinfunction "P9_1_59") (pintype "bidirectional"))
    )
    (net (code "74") (name "P9_05") (class "Default")
      (node (ref "J7") (pin "P$2") (pinfunction "P$2_P$2") (pintype "bidirectional"))
      (node (ref "U5") (pin "73") (pinfunction "P9_5_73") (pintype "bidirectional"))
    )
    (net (code "75") (name "P9_06") (class "Default")
      (node (ref "J7") (pin "P$1") (pinfunction "P$1_P$1") (pintype "bidirectional"))
      (node (ref "U5") (pin "72") (pinfunction "P9_6_72") (pintype "bidirectional"))
    )
    (net (code "76") (name "P9_07") (class "Default")
      (node (ref "J7") (pin "P$3") (pinfunction "P$3_P$3") (pintype "bidirectional"))
      (node (ref "U5") (pin "71") (pinfunction "P9_7_71") (pintype "bidirectional"))
    )
    (net (code "77") (name "P9_08") (class "Default")
      (node (ref "J7") (pin "P$5") (pinfunction "P$5_P$5") (pintype "bidirectional"))
      (node (ref "U5") (pin "70") (pinfunction "P9_8_70") (pintype "bidirectional"))
    )
    (net (code "78") (name "P009_AN004") (class "Default")
      (node (ref "J8") (pin "P$15") (pinfunction "P$15_P$15") (pintype "bidirectional"))
      (node (ref "U5") (pin "160") (pinfunction "P0_9/AN004_160") (pintype "bidirectional"))
    )
    (net (code "79") (name "P014_DA0_AN005_AN105") (class "Default")
      (node (ref "J8") (pin "P$17") (pinfunction "P$17_P$17") (pintype "bidirectional"))
      (node (ref "U5") (pin "152") (pinfunction "P0_14/DA0/AN005/AN105_152") (pintype "bidirectional"))
    )
    (net (code "80") (name "P015_DA1_AN006_AN106") (class "Default")
      (node (ref "J8") (pin "P$19") (pinfunction "P$19_P$19") (pintype "bidirectional"))
      (node (ref "U5") (pin "151") (pinfunction "P0_15/DA1/AN006/AN106_151") (pintype "bidirectional"))
    )
    (net (code "81") (name "P400_ADC") (class "Default")
      (node (ref "U5") (pin "1") (pinfunction "P4_0_1") (pintype "bidirectional"))
    )
    (net (code "82") (name "RELAY_1") (class "Default")
      (node (ref "J4") (pin "P$15") (pinfunction "P$15_P$15") (pintype "bidirectional"))
      (node (ref "U5") (pin "68") (pinfunction "P2_1/MD_68") (pintype "bidirectional"))
    )
    (net (code "83") (name "RELAY_2") (class "Default")
      (node (ref "J4") (pin "P$17") (pinfunction "P$17_P$17") (pintype "bidirectional"))
      (node (ref "U5") (pin "54") (pinfunction "P2_2_54") (pintype "bidirectional"))
    )
    (net (code "84") (name "RELAY_3") (class "Default")
      (node (ref "J4") (pin "P$19") (pinfunction "P$19_P$19") (pintype "bidirectional"))
      (node (ref "U5") (pin "53") (pinfunction "P2_3_53") (pintype "bidirectional"))
    )
    (net (code "85") (name "RELAY_4") (class "Default")
      (node (ref "J4") (pin "P$20") (pinfunction "P$20_P$20") (pintype "bidirectional"))
      (node (ref "U5") (pin "52") (pinfunction "P2_4_52") (pintype "bidirectional"))
    )
    (net (code "86") (name "RESET") (class "Default")
      (node (ref "C29") (pin "P$1") (pinfunction "1_P$1") (pintype "passive"))
      (node (ref "J1") (pin "9") (pinfunction "9_9") (pintype "passive"))
      (node (ref "R10") (pin "P$1") (pinfunction "1_P$1") (pintype "passive"))
      (node (ref "U5") (pin "67") (pinfunction "RES#_67") (pintype "bidirectional"))
    )
    (net (code "87") (name "TCK") (class "Default")
      (node (ref "J1") (pin "7") (pinfunction "7_7") (pintype "passive"))
      (node (ref "U5") (pin "88") (pinfunction "P3_0_88") (pintype "bidirectional"))
    )
    (net (code "88") (name "TDI") (class "Default")
      (node (ref "J1") (pin "1") (pinfunction "1_1") (pintype "passive"))
      (node (ref "U5") (pin "91") (pinfunction "P1_10_91") (pintype "bidirectional"))
    )
    (net (code "89") (name "TDO") (class "Default")
      (node (ref "J1") (pin "3") (pinfunction "3_3") (pintype "passive"))
      (node (ref "U5") (pin "90") (pinfunction "P1_9_90") (pintype "bidirectional"))
    )
    (net (code "90") (name "TMS") (class "Default")
      (node (ref "J1") (pin "5") (pinfunction "5_5") (pintype "passive"))
      (node (ref "U5") (pin "89") (pinfunction "P1_8_89") (pintype "bidirectional"))
    )
    (net (code "91") (name "USBHS_FAULT") (class "Default")
      (node (ref "R2") (pin "P$1") (pinfunction "1_P$1") (pintype "passive"))
      (node (ref "U2") (pin "3") (pinfunction "FLG_3") (pintype "input"))
      (node (ref "U5") (pin "78") (pinfunction "P3_8_78") (pintype "bidirectional"))
    )
    (net (code "92") (name "USBHS_N") (class "Default")
      (node (ref "J2") (pin "D-") (pinfunction "D-_D-") (pintype "bidirectional"))
      (node (ref "U5") (pin "31") (pinfunction "USBHS_DM_31") (pintype "bidirectional"))
    )
    (net (code "93") (name "USBHS_P") (class "Default")
      (node (ref "J2") (pin "D+") (pinfunction "D+_D+") (pintype "bidirectional"))
      (node (ref "U5") (pin "32") (pinfunction "USBHS_DP_32") (pintype "bidirectional"))
    )
    (net (code "94") (name "USBHS_VBUS") (class "Default")
      (node (ref "C15") (pin "P$1") (pinfunction "1_P$1") (pintype "passive"))
      (node (ref "C18") (pin "1") (pinfunction "1_1") (pintype "passive"))
      (node (ref "J2") (pin "VBUS") (pinfunction "VBUS_VBUS") (pintype "power_in"))
      (node (ref "U2") (pin "5") (pinfunction "OUT_5") (pintype "input"))
      (node (ref "U5") (pin "17") (pinfunction "PB_1_17") (pintype "bidirectional"))
    )
    (net (code "95") (name "USBHS_VBUSEN") (class "Default")
      (node (ref "R3") (pin "P$1") (pinfunction "1_P$1") (pintype "passive"))
      (node (ref "U2") (pin "1") (pinfunction "EN_1") (pintype "input"))
      (node (ref "U5") (pin "16") (pinfunction "PB_0_16") (pintype "bidirectional"))
    )
    (net (code "96") (name "USB_N") (class "Default")
      (node (ref "R5") (pin "P$1") (pinfunction "1_P$1") (pintype "passive"))
      (node (ref "U5") (pin "46") (pinfunction "USB_DM_46") (pintype "bidirectional"))
    )
    (net (code "97") (name "USB_P") (class "Default")
      (node (ref "R6") (pin "P$1") (pinfunction "1_P$1") (pintype "passive"))
      (node (ref "U5") (pin "47") (pinfunction "USB_DP_47") (pintype "bidirectional"))
    )
    (net (code "98") (name "USB_VBUS_B") (class "Default")
      (node (ref "R4") (pin "P$1") (pinfunction "1_P$1") (pintype "passive"))
      (node (ref "U5") (pin "44") (pinfunction "P4_7_44") (pintype "bidirectional"))
    )
    (net (code "99") (name "VCL_F(FLASH)") (class "Default")
      (node (ref "C21") (pin "P$2") (pinfunction "2_P$2") (pintype "passive"))
      (node (ref "U5") (pin "112") (pinfunction "VCL_F(FLASH)_112") (pintype "bidirectional"))
    )
    (net (code "100") (name "VDD") (class "Default")
      (node (ref "C10") (pin "P$2") (pinfunction "2_P$2") (pintype "passive"))
      (node (ref "C12") (pin "P$2") (pinfunction "2_P$2") (pintype "passive"))
      (node (ref "C13") (pin "P$2") (pinfunction "2_P$2") (pintype "passive"))
      (node (ref "C17") (pin "P$2") (pinfunction "2_P$2") (pintype "passive"))
      (node (ref "C2") (pin "P$1") (pinfunction "1_P$1") (pintype "passive"))
      (node (ref "C22") (pin "P$2") (pinfunction "2_P$2") (pintype "passive"))
      (node (ref "C23") (pin "P$1") (pinfunction "1_P$1") (pintype "passive"))
      (node (ref "C25") (pin "P$2") (pinfunction "2_P$2") (pintype "passive"))
      (node (ref "C26") (pin "P$1") (pinfunction "1_P$1") (pintype "passive"))
      (node (ref "C27") (pin "P$1") (pinfunction "1_P$1") (pintype "passive"))
      (node (ref "C3") (pin "P$1") (pinfunction "1_P$1") (pintype "passive"))
      (node (ref "C30") (pin "P$1") (pinfunction "1_P$1") (pintype "passive"))
      (node (ref "C31") (pin "P$2") (pinfunction "2_P$2") (pintype "passive"))
      (node (ref "C4") (pin "P$1") (pinfunction "1_P$1") (pintype "passive"))
      (node (ref "C6") (pin "P$2") (pinfunction "2_P$2") (pintype "passive"))
      (node (ref "J1") (pin "2") (pinfunction "2_2") (pintype "passive"))
      (node (ref "J1") (pin "4") (pinfunction "4_4") (pintype "passive"))
      (node (ref "L1") (pin "2") (pinfunction "P$2_2") (pintype "bidirectional"))
      (node (ref "R1") (pin "P$2") (pinfunction "2_P$2") (pintype "passive"))
      (node (ref "R10") (pin "P$2") (pinfunction "2_P$2") (pintype "passive"))
      (node (ref "U1") (pin "P3") (pinfunction "VDD1_P3") (pintype "bidirectional"))
      (node (ref "U1") (pin "P4") (pinfunction "VDD_P4") (pintype "bidirectional"))
      (node (ref "U5") (pin "110") (pinfunction "VCC(IO)5_110") (pintype "bidirectional"))
      (node (ref "U5") (pin "123") (pinfunction "VCC(IO)6_123") (pintype "bidirectional"))
      (node (ref "U5") (pin "138") (pinfunction "VCC(IO)7_138") (pintype "bidirectional"))
      (node (ref "U5") (pin "149") (pinfunction "VCC(IO)8_149") (pintype "bidirectional"))
      (node (ref "U5") (pin "155") (pinfunction "AVCC0_155") (pintype "bidirectional"))
      (node (ref "U5") (pin "171") (pinfunction "VCC(IO)9_171") (pintype "bidirectional"))
      (node (ref "U5") (pin "25") (pinfunction "VCC1_25") (pintype "bidirectional"))
      (node (ref "U5") (pin "26") (pinfunction "AVCC_SUBHS_26") (pintype "bidirectional"))
      (node (ref "U5") (pin "34") (pinfunction "VCC_USBHS_34") (pintype "bidirectional"))
      (node (ref "U5") (pin "48") (pinfunction "VCC_USB_48") (pintype "bidirectional"))
      (node (ref "U5") (pin "61") (pinfunction "VCC(IO)2_61") (pintype "bidirectional"))
      (node (ref "U5") (pin "84") (pinfunction "VCC(IO)3_84") (pintype "bidirectional"))
      (node (ref "U5") (pin "97") (pinfunction "VCC(IO)4_97") (pintype "bidirectional"))
    )
    (net (code "101") (name "VDD5") (class "Default")
      (node (ref "C11") (pin "P$1") (pinfunction "1_P$1") (pintype "passive"))
      (node (ref "C8") (pin "P$1") (pinfunction "1_P$1") (pintype "passive"))
      (node (ref "J3") (pin "P$3") (pinfunction "P$3_P$3") (pintype "bidirectional"))
      (node (ref "R2") (pin "P$2") (pinfunction "2_P$2") (pintype "passive"))
      (node (ref "R3") (pin "P$2") (pinfunction "2_P$2") (pintype "passive"))
      (node (ref "U2") (pin "4") (pinfunction "VIN_4") (pintype "input"))
    )
    (net (code "102") (name "VDDIN") (class "Default")
      (node (ref "J3") (pin "P$2") (pinfunction "P$2_P$2") (pintype "bidirectional"))
      (node (ref "L1") (pin "1") (pinfunction "P$1_1") (pintype "bidirectional"))
    )
    (net (code "103") (name "XCIN") (class "Default")
      (node (ref "C19") (pin "P$1") (pinfunction "1_P$1") (pintype "passive"))
      (node (ref "U5") (pin "20") (pinfunction "XCIN_20") (pintype "bidirectional"))
      (node (ref "X2") (pin "P$1") (pinfunction "P$1_P$1") (pintype "bidirectional"))
    )
    (net (code "104") (name "XCOUT") (class "Default")
      (node (ref "C24") (pin "P$1") (pinfunction "1_P$1") (pintype "passive"))
      (node (ref "U5") (pin "21") (pinfunction "XCOUT_21") (pintype "bidirectional"))
      (node (ref "X2") (pin "P$2") (pinfunction "P$2_P$2") (pintype "bidirectional"))
    )
    (net (code "105") (name "XTAL1") (class "Default")
      (node (ref "C7") (pin "P$1") (pinfunction "1_P$1") (pintype "passive"))
      (node (ref "U5") (pin "23") (pinfunction "P2_13/XTAL_23") (pintype "bidirectional"))
      (node (ref "X1") (pin "1") (pinfunction "1_1") (pintype "bidirectional"))
    )
    (net (code "106") (name "XTAL2") (class "Default")
      (node (ref "C14") (pin "P$1") (pinfunction "1_P$1") (pintype "passive"))
      (node (ref "U5") (pin "24") (pinfunction "P2_12/EXTAL_24") (pintype "bidirectional"))
      (node (ref "X1") (pin "3") (pinfunction "3_3") (pintype "bidirectional"))
    )
    (net (code "107") (name "X_DIR") (class "Default")
      (node (ref "J4") (pin "P$3") (pinfunction "P$3_P$3") (pintype "bidirectional"))
      (node (ref "U5") (pin "118") (pinfunction "P6_4_118") (pintype "bidirectional"))
    )
    (net (code "108") (name "X_LS") (class "Default")
      (node (ref "J4") (pin "P$2") (pinfunction "P$2_P$2") (pintype "bidirectional"))
      (node (ref "U5") (pin "164") (pinfunction "P0_5/AN101_164") (pintype "bidirectional"))
    )
    (net (code "109") (name "X_STEP") (class "Default")
      (node (ref "J4") (pin "P$11") (pinfunction "P$11_P$11") (pintype "bidirectional"))
      (node (ref "U5") (pin "86") (pinfunction "P3_2_86") (pintype "bidirectional"))
    )
    (net (code "110") (name "Y_DIR") (class "Default")
      (node (ref "J4") (pin "P$5") (pinfunction "P$5_P$5") (pintype "bidirectional"))
      (node (ref "U5") (pin "115") (pinfunction "P6_7_115") (pintype "bidirectional"))
    )
    (net (code "111") (name "Y_LS") (class "Default")
      (node (ref "J4") (pin "P$4") (pinfunction "P$4_P$4") (pintype "bidirectional"))
      (node (ref "U5") (pin "175") (pinfunction "P5_12_175") (pintype "bidirectional"))
    )
    (net (code "112") (name "Y_STEP") (class "Default")
      (node (ref "J4") (pin "P$13") (pinfunction "P$13_P$13") (pintype "bidirectional"))
      (node (ref "U5") (pin "82") (pinfunction "P3_4_82") (pintype "bidirectional"))
    )
    (net (code "113") (name "Z_DIR") (class "Default")
      (node (ref "J4") (pin "P$1") (pinfunction "P$1_P$1") (pintype "bidirectional"))
      (node (ref "U5") (pin "121") (pinfunction "P6_1_121") (pintype "bidirectional"))
    )
    (net (code "114") (name "Z_LS") (class "Default")
      (node (ref "J4") (pin "P$6") (pinfunction "P$6_P$6") (pintype "bidirectional"))
      (node (ref "U5") (pin "169") (pinfunction "P0_0/AN0\\00_169") (pintype "bidirectional"))
    )
    (net (code "115") (name "Z_STEP") (class "Default")
      (node (ref "J4") (pin "P$9") (pinfunction "P$9_P$9") (pintype "bidirectional"))
      (node (ref "U5") (pin "92") (pinfunction "P1_11_92") (pintype "bidirectional"))
    )
    (net (code "116") (name "unconnected-(U5-P1_2-Pad130)") (class "Default")
      (node (ref "U5") (pin "130") (pinfunction "P1_2_130") (pintype "bidirectional"))
    )
    (net (code "117") (name "unconnected-(U5-P1_3-Pad129)") (class "Default")
      (node (ref "U5") (pin "129") (pinfunction "P1_3_129") (pintype "bidirectional"))
    )
    (net (code "118") (name "unconnected-(U5-P1_4-Pad128)") (class "Default")
      (node (ref "U5") (pin "128") (pinfunction "P1_4_128") (pintype "bidirectional"))
    )
    (net (code "119") (name "unconnected-(U5-P1_5-Pad127)") (class "Default")
      (node (ref "U5") (pin "127") (pinfunction "P1_5_127") (pintype "bidirectional"))
    )
    (net (code "120") (name "unconnected-(U5-P1_6-Pad126)") (class "Default")
      (node (ref "U5") (pin "126") (pinfunction "P1_6_126") (pintype "bidirectional"))
    )
    (net (code "121") (name "unconnected-(U5-P1_7-Pad125)") (class "Default")
      (node (ref "U5") (pin "125") (pinfunction "P1_7_125") (pintype "bidirectional"))
    )
    (net (code "122") (name "unconnected-(U5-P1_15-Pad96)") (class "Default")
      (node (ref "U5") (pin "96") (pinfunction "P1_15_96") (pintype "bidirectional"))
    )
    (net (code "123") (name "unconnected-(U5-P4_1-Pad2)") (class "Default")
      (node (ref "U5") (pin "2") (pinfunction "P4_1_2") (pintype "bidirectional"))
    )
    (net (code "124") (name "unconnected-(U5-P4_2-Pad3)") (class "Default")
      (node (ref "U5") (pin "3") (pinfunction "P4_2_3") (pintype "bidirectional"))
    )
    (net (code "125") (name "unconnected-(U5-P4_8-Pad43)") (class "Default")
      (node (ref "U5") (pin "43") (pinfunction "P4_8_43") (pintype "bidirectional"))
    )
    (net (code "126") (name "unconnected-(U5-P4_10-Pad41)") (class "Default")
      (node (ref "U5") (pin "41") (pinfunction "P4_10_41") (pintype "bidirectional"))
    )
    (net (code "127") (name "unconnected-(U5-P4_11-Pad40)") (class "Default")
      (node (ref "U5") (pin "40") (pinfunction "P4_11_40") (pintype "bidirectional"))
    )
    (net (code "128") (name "unconnected-(U5-P4_12-Pad39)") (class "Default")
      (node (ref "U5") (pin "39") (pinfunction "P4_12_39") (pintype "bidirectional"))
    )
    (net (code "129") (name "unconnected-(U5-P4_13-Pad38)") (class "Default")
      (node (ref "U5") (pin "38") (pinfunction "P4_13_38") (pintype "bidirectional"))
    )
    (net (code "130") (name "unconnected-(U5-P4_14-Pad37)") (class "Default")
      (node (ref "U5") (pin "37") (pinfunction "P4_14_37") (pintype "bidirectional"))
    )
    (net (code "131") (name "unconnected-(U5-P4_15-Pad36)") (class "Default")
      (node (ref "U5") (pin "36") (pinfunction "P4_15_36") (pintype "bidirectional"))
    )
    (net (code "132") (name "unconnected-(U5-P6_0-Pad122)") (class "Default")
      (node (ref "U5") (pin "122") (pinfunction "P6_0_122") (pintype "bidirectional"))
    )
    (net (code "133") (name "unconnected-(U5-P6_2-Pad120)") (class "Default")
      (node (ref "U5") (pin "120") (pinfunction "P6_2_120") (pintype "bidirectional"))
    )
    (net (code "134") (name "unconnected-(U5-P6_3-Pad119)") (class "Default")
      (node (ref "U5") (pin "119") (pinfunction "P6_3_119") (pintype "bidirectional"))
    )
    (net (code "135") (name "unconnected-(U5-P6_5-Pad117)") (class "Default")
      (node (ref "U5") (pin "117") (pinfunction "P6_5_117") (pintype "bidirectional"))
    )
    (net (code "136") (name "unconnected-(U5-P6_6-Pad116)") (class "Default")
      (node (ref "U5") (pin "116") (pinfunction "P6_6_116") (pintype "bidirectional"))
    )
    (net (code "137") (name "unconnected-(U5-P6_8-Pad99)") (class "Default")
      (node (ref "U5") (pin "99") (pinfunction "P6_8_99") (pintype "bidirectional"))
    )
    (net (code "138") (name "unconnected-(U5-P6_9-Pad100)") (class "Default")
      (node (ref "U5") (pin "100") (pinfunction "P6_9_100") (pintype "bidirectional"))
    )
    (net (code "139") (name "unconnected-(U5-P6_11-Pad102)") (class "Default")
      (node (ref "U5") (pin "102") (pinfunction "P6_11_102") (pintype "bidirectional"))
    )
    (net (code "140") (name "unconnected-(U5-P6_12-Pad103)") (class "Default")
      (node (ref "U5") (pin "103") (pinfunction "P6_12_103") (pintype "bidirectional"))
    )
    (net (code "141") (name "unconnected-(U5-P6_13-Pad104)") (class "Default")
      (node (ref "U5") (pin "104") (pinfunction "P6_13_104") (pintype "bidirectional"))
    )
    (net (code "142") (name "unconnected-(U5-P6_14-Pad105)") (class "Default")
      (node (ref "U5") (pin "105") (pinfunction "P6_14_105") (pintype "bidirectional"))
    )
    (net (code "143") (name "unconnected-(U5-P6_15-Pad106)") (class "Default")
      (node (ref "U5") (pin "106") (pinfunction "P6_15_106") (pintype "bidirectional"))
    )
    (net (code "144") (name "unconnected-(U5-P7_6-Pad14)") (class "Default")
      (node (ref "U5") (pin "14") (pinfunction "P7_6_14") (pintype "bidirectional"))
    )
    (net (code "145") (name "unconnected-(U5-P7_7-Pad15)") (class "Default")
      (node (ref "U5") (pin "15") (pinfunction "P7_7_15") (pintype "bidirectional"))
    )
    (net (code "146") (name "unconnected-(U5-PA_0-Pad114)") (class "Default")
      (node (ref "U5") (pin "114") (pinfunction "PA_0_114") (pintype "bidirectional"))
    )
    (net (code "147") (name "unconnected-(U5-PA_1-Pad113)") (class "Default")
      (node (ref "U5") (pin "113") (pinfunction "PA_1_113") (pintype "bidirectional"))
    )
    (net (code "148") (name "unconnected-(U5-PA_8-Pad107)") (class "Default")
      (node (ref "U5") (pin "107") (pinfunction "PA_8_107") (pintype "bidirectional"))
    )
    (net (code "149") (name "unconnected-(U5-PA_9-Pad108)") (class "Default")
      (node (ref "U5") (pin "108") (pinfunction "PA_9_108") (pintype "bidirectional"))
    )
    (net (code "150") (name "unconnected-(U5-PA_10-Pad109)") (class "Default")
      (node (ref "U5") (pin "109") (pinfunction "PA_10_109") (pintype "bidirectional"))
    )
    (net (code "151") (name "unconnected-(U5-VBAT-Pad18)") (class "Default")
      (node (ref "U5") (pin "18") (pinfunction "VBAT_18") (pintype "bidirectional"))
    )
    (net (code "152") (name "unconnected-(U5-VREFH-Pad154)") (class "Default")
      (node (ref "U5") (pin "154") (pinfunction "VREFH_154") (pintype "bidirectional"))
    )
    (net (code "153") (name "unconnected-(U5-VREFH0-Pad158)") (class "Default")
      (node (ref "U5") (pin "158") (pinfunction "VREFH0_158") (pintype "bidirectional"))
    )
    (net (code "154") (name "unconnected-(U5-VREFL-Pad153)") (class "Default")
      (node (ref "U5") (pin "153") (pinfunction "VREFL_153") (pintype "bidirectional"))
    )
    (net (code "155") (name "unconnected-(U5-VREFL0-Pad157)") (class "Default")
      (node (ref "U5") (pin "157") (pinfunction "VREFL0_157") (pintype "bidirectional"))
    )
  )
)
